# piezo-preamp-tickler_V2-RevD.net
KiCad netlist of a schematic drawn in EAGLE
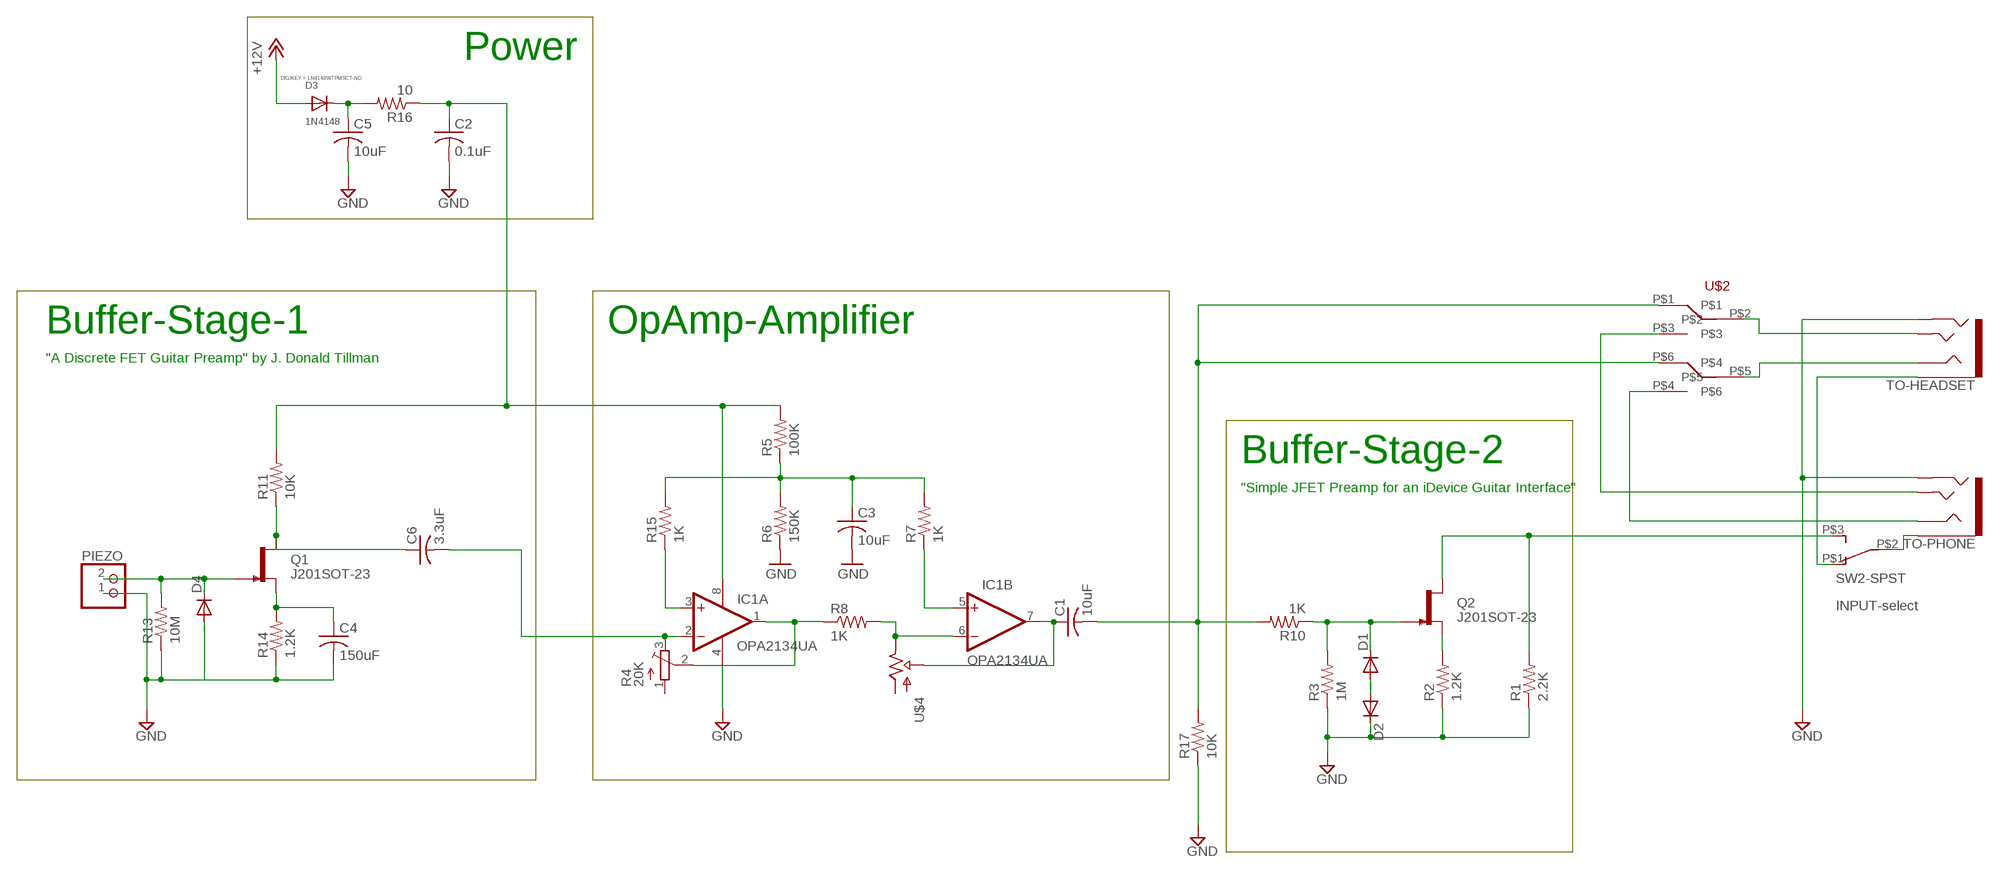
[diagram p0: schematic, sheet 1]
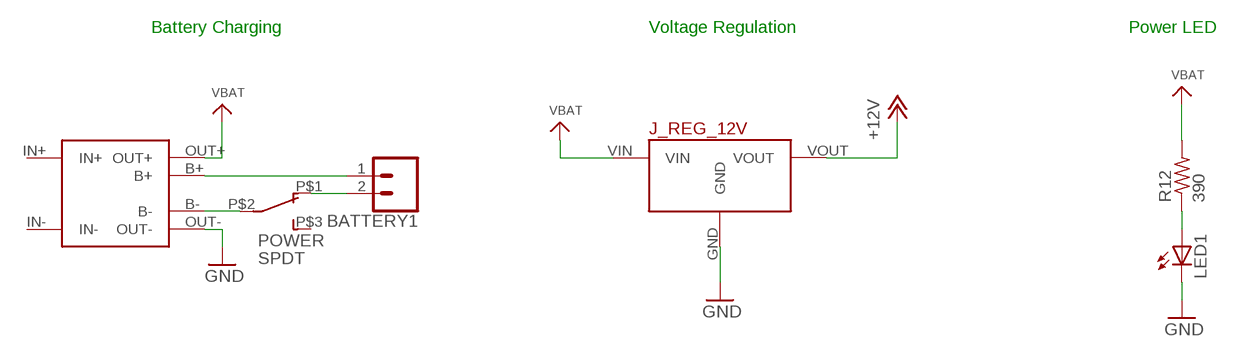
[diagram p1: schematic, sheet 2]

(export (version "E")
  (design (tool "Eeschema 10.0.6"))
  (components
    (comp (ref "BATTERY1")
      (value "CONN_02LOCK")
      (footprint "eagle-import:1X02_LOCK")
      (libsource (lib "eagle-import") (part "CONN_02LOCK"))
    )
    (comp (ref "J_REG_12V")
      (value "POLOLU_VOLTAGE_REGULATORS_3PIN")
      (footprint "eagle-import:POLOLU_5V-12V_STEPUP_U3V12F5-U3V12F12")
      (libsource (lib "eagle-import") (part "POLOLU_VOLTAGE_REGULATORS_3PIN"))
    )
    (comp (ref "LED1")
      (value "LED3MM")
      (footprint "eagle-import:LED3MM")
      (libsource (lib "eagle-import") (part "LED3MM"))
    )
    (comp (ref "POWER")
      (value "SPDT")
      (footprint "eagle-import:SWITCH_SPDT_CL-SB-12B")
      (libsource (lib "eagle-import") (part "SWITCH_SPDTCL-SB-12B"))
    )
    (comp (ref "R12")
      (value "390")
      (footprint "eagle-import:R0805")
      (libsource (lib "eagle-import") (part "R-US_R0805"))
    )
    (comp (ref "USB-LIPO-CHARGER")
      (value "TP4056-MODULE")
      (footprint "eagle-import:TP4056-LITHIUM-PROTECTED-MODULE")
      (libsource (lib "eagle-import") (part "TP4056-MODULE"))
    )
    (comp (ref "C1")
      (value "10uF")
      (footprint "eagle-import:C0805K")
      (libsource (lib "eagle-import") (part "C-USC0805K"))
    )
    (comp (ref "C2")
      (value "0.1uF")
      (footprint "eagle-import:C0805K")
      (libsource (lib "eagle-import") (part "C-USC0805K"))
    )
    (comp (ref "C3")
      (value "10uF")
      (footprint "eagle-import:C0805K")
      (libsource (lib "eagle-import") (part "C-USC0805K"))
    )
    (comp (ref "C4")
      (value "150uF")
      (footprint "eagle-import:C3216")
      (libsource (lib "eagle-import") (part "C-USC3216"))
    )
    (comp (ref "C5")
      (value "10uF")
      (footprint "eagle-import:C0805K")
      (libsource (lib "eagle-import") (part "C-USC0805K"))
    )
    (comp (ref "C6")
      (value "3.3uF")
      (footprint "eagle-import:C0805K")
      (libsource (lib "eagle-import") (part "C-USC0805K"))
    )
    (comp (ref "D1")
      (value "DIODE-SOD123")
      (footprint "eagle-import:SOD123")
      (libsource (lib "eagle-import") (part "DIODE-SOD123"))
    )
    (comp (ref "D2")
      (value "DIODE-SOD123")
      (footprint "eagle-import:SOD123")
      (libsource (lib "eagle-import") (part "DIODE-SOD123"))
    )
    (comp (ref "D3")
      (value "1N4148")
      (footprint "eagle-import:SOD-123")
      (fields (field (name "DIGIKEY") "1N4148WTPMSCT-ND"))
      (libsource (lib "eagle-import") (part "DIODESOD-123"))
    )
    (comp (ref "D4")
      (value "DIODE-SOD123")
      (footprint "eagle-import:SOD123")
      (libsource (lib "eagle-import") (part "DIODE-SOD123"))
    )
    (comp (ref "IC1")
      (value "OPA2134UA")
      (footprint "eagle-import:SO08")
      (libsource (lib "eagle-import") (part "OPA2UA134"))
    )
    (comp (ref "PIEZO")
      (value "JST_2PIN-THM")
      (footprint "eagle-import:JST-PH-2-THM")
      (libsource (lib "eagle-import") (part "JST_2PIN-THM"))
    )
    (comp (ref "Q1")
      (value "J201SOT-23")
      (footprint "eagle-import:SOT23-3")
      (libsource (lib "eagle-import") (part "J201SOT-23"))
    )
    (comp (ref "Q2")
      (value "J201SOT-23")
      (footprint "eagle-import:SOT23-3")
      (libsource (lib "eagle-import") (part "J201SOT-23"))
    )
    (comp (ref "R1")
      (value "2.2K")
      (footprint "eagle-import:R0603")
      (libsource (lib "eagle-import") (part "R-US_R0603"))
    )
    (comp (ref "R2")
      (value "1.2K")
      (footprint "eagle-import:R0603")
      (libsource (lib "eagle-import") (part "R-US_R0603"))
    )
    (comp (ref "R3")
      (value "1M")
      (footprint "eagle-import:R0603")
      (libsource (lib "eagle-import") (part "R-US_R0603"))
    )
    (comp (ref "R4")
      (value "20K")
      (footprint "eagle-import:TC33X")
      (libsource (lib "eagle-import") (part "TRIMPOTTC33X"))
    )
    (comp (ref "R5")
      (value "100K")
      (footprint "eagle-import:R0603")
      (libsource (lib "eagle-import") (part "R-US_R0603"))
    )
    (comp (ref "R6")
      (value "150K")
      (footprint "eagle-import:R0603")
      (libsource (lib "eagle-import") (part "R-US_R0603"))
    )
    (comp (ref "R7")
      (value "1K")
      (footprint "eagle-import:R0603")
      (libsource (lib "eagle-import") (part "R-US_R0603"))
    )
    (comp (ref "R8")
      (value "1K")
      (footprint "eagle-import:R0603")
      (libsource (lib "eagle-import") (part "R-US_R0603"))
    )
    (comp (ref "R10")
      (value "1K")
      (footprint "eagle-import:R0603")
      (libsource (lib "eagle-import") (part "R-US_R0603"))
    )
    (comp (ref "R11")
      (value "10K")
      (footprint "eagle-import:R0603")
      (libsource (lib "eagle-import") (part "R-US_R0603"))
    )
    (comp (ref "R13")
      (value "10M")
      (footprint "eagle-import:R0603")
      (libsource (lib "eagle-import") (part "R-US_R0603"))
    )
    (comp (ref "R14")
      (value "1.2K")
      (footprint "eagle-import:R0603")
      (libsource (lib "eagle-import") (part "R-US_R0603"))
    )
    (comp (ref "R15")
      (value "1K")
      (footprint "eagle-import:R0603")
      (libsource (lib "eagle-import") (part "R-US_R0603"))
    )
    (comp (ref "R16")
      (value "10")
      (footprint "eagle-import:R0603")
      (libsource (lib "eagle-import") (part "R-US_R0603"))
    )
    (comp (ref "R17")
      (value "10K")
      (footprint "eagle-import:R0603")
      (libsource (lib "eagle-import") (part "R-US_R0603"))
    )
    (comp (ref "SW2-SPST")
      (value "INPUT-select")
      (footprint "eagle-import:SWITCH_SPDT_CL-SB-12B")
      (libsource (lib "eagle-import") (part "SWITCH_SPDTCL-SB-12B"))
    )
    (comp (ref "TO-HEADSET")
      (value "AUDIO-JACK3LGPADS")
      (footprint "eagle-import:AUDIO-JACK-TRRS-SMD")
      (libsource (lib "eagle-import") (part "AUDIO-JACK3LGPADS"))
    )
    (comp (ref "TO-PHONE")
      (value "AUDIO-JACK3LGPADS")
      (footprint "eagle-import:AUDIO-JACK-TRRS-SMD")
      (libsource (lib "eagle-import") (part "AUDIO-JACK3LGPADS"))
    )
    (comp (ref "U$2")
      (value "SWITCH_DPDT")
      (footprint "eagle-import:SWITCH_DPDT_CL-SB-12B")
      (libsource (lib "eagle-import") (part "SWITCH_DPDT"))
    )
    (comp (ref "U$4")
      (value "POT")
      (footprint "eagle-import:ALPS_POT")
      (libsource (lib "eagle-import") (part "POT"))
    )
  )
  (nets
    (net (code "1") (name "+12V") (class "Default")
      (node (ref "D3") (pin "A") (pinfunction "A_A") (pintype "passive"))
      (node (ref "J_REG_12V") (pin "VOUT") (pinfunction "VOUT_VOUT") (pintype "bidirectional"))
    )
    (net (code "2") (name "GND") (class "Default")
      (node (ref "C2") (pin "2") (pinfunction "2_2") (pintype "passive"))
      (node (ref "C3") (pin "2") (pinfunction "2_2") (pintype "passive"))
      (node (ref "C4") (pin "2") (pinfunction "2_2") (pintype "passive"))
      (node (ref "C5") (pin "2") (pinfunction "2_2") (pintype "passive"))
      (node (ref "D2") (pin "C") (pinfunction "C_C") (pintype "passive"))
      (node (ref "D4") (pin "A") (pinfunction "A_A") (pintype "passive"))
      (node (ref "IC1") (pin "4") (pinfunction "V-_4") (pintype "power_in"))
      (node (ref "J_REG_12V") (pin "GND") (pinfunction "GND_GND") (pintype "bidirectional"))
      (node (ref "LED1") (pin "K") (pinfunction "C_K") (pintype "passive"))
      (node (ref "PIEZO") (pin "1") (pinfunction "2_1") (pintype "passive"))
      (node (ref "R1") (pin "1") (pinfunction "1_1") (pintype "passive"))
      (node (ref "R13") (pin "1") (pinfunction "1_1") (pintype "passive"))
      (node (ref "R14") (pin "1") (pinfunction "1_1") (pintype "passive"))
      (node (ref "R17") (pin "1") (pinfunction "1_1") (pintype "passive"))
      (node (ref "R2") (pin "1") (pinfunction "1_1") (pintype "passive"))
      (node (ref "R3") (pin "1") (pinfunction "1_1") (pintype "passive"))
      (node (ref "R6") (pin "1") (pinfunction "1_1") (pintype "passive"))
      (node (ref "TO-HEADSET") (pin "RING2") (pinfunction "RING2_RING2") (pintype "bidirectional"))
      (node (ref "TO-PHONE") (pin "RING2") (pinfunction "RING2_RING2") (pintype "bidirectional"))
      (node (ref "USB-LIPO-CHARGER") (pin "OUT-") (pinfunction "OUT-_OUT-") (pintype "power_in"))
    )
    (net (code "3") (name "IN+") (class "Default")
      (node (ref "USB-LIPO-CHARGER") (pin "IN+") (pinfunction "IN+_IN+") (pintype "power_in"))
    )
    (net (code "4") (name "IN-") (class "Default")
      (node (ref "USB-LIPO-CHARGER") (pin "IN-") (pinfunction "IN-_IN-") (pintype "power_in"))
    )
    (net (code "5") (name "Net-(BATTERY1-Pad1)") (class "Default")
      (node (ref "BATTERY1") (pin "1") (pinfunction "1_1") (pintype "passive"))
      (node (ref "USB-LIPO-CHARGER") (pin "B+") (pinfunction "B+_B+") (pintype "power_in"))
    )
    (net (code "6") (name "Net-(C3-Pad1)") (class "Default")
      (node (ref "C3") (pin "1") (pinfunction "1_1") (pintype "passive"))
      (node (ref "R15") (pin "2") (pinfunction "2_2") (pintype "passive"))
      (node (ref "R5") (pin "1") (pinfunction "1_1") (pintype "passive"))
      (node (ref "R6") (pin "2") (pinfunction "2_2") (pintype "passive"))
      (node (ref "R7") (pin "2") (pinfunction "2_2") (pintype "passive"))
    )
    (net (code "7") (name "Net-(C5-Pad1)") (class "Default")
      (node (ref "C5") (pin "1") (pinfunction "1_1") (pintype "passive"))
      (node (ref "D3") (pin "C") (pinfunction "C_C") (pintype "passive"))
      (node (ref "R16") (pin "2") (pinfunction "2_2") (pintype "passive"))
    )
    (net (code "8") (name "Net-(D1-PadA)") (class "Default")
      (node (ref "D1") (pin "A") (pinfunction "A_A") (pintype "passive"))
      (node (ref "D2") (pin "A") (pinfunction "A_A") (pintype "passive"))
    )
    (net (code "9") (name "Net-(IC1A-+IN)") (class "Default")
      (node (ref "IC1") (pin "3") (pinfunction "+IN_3") (pintype "input"))
      (node (ref "R15") (pin "1") (pinfunction "1_1") (pintype "passive"))
    )
    (net (code "10") (name "Net-(IC1A--IN)") (class "Default")
      (node (ref "C6") (pin "2") (pinfunction "2_2") (pintype "passive"))
      (node (ref "IC1") (pin "2") (pinfunction "-IN_2") (pintype "input"))
      (node (ref "R4") (pin "3") (pinfunction "E_3") (pintype "passive"))
    )
    (net (code "11") (name "Net-(IC1A-OUT)") (class "Default")
      (node (ref "IC1") (pin "1") (pinfunction "OUT_1") (pintype "output"))
      (node (ref "R4") (pin "2") (pinfunction "S_2") (pintype "passive"))
      (node (ref "R8") (pin "1") (pinfunction "1_1") (pintype "passive"))
    )
    (net (code "12") (name "Net-(IC1A-V+)") (class "Default")
      (node (ref "C2") (pin "1") (pinfunction "1_1") (pintype "passive"))
      (node (ref "IC1") (pin "8") (pinfunction "V+_8") (pintype "power_in"))
      (node (ref "R11") (pin "2") (pinfunction "2_2") (pintype "passive"))
      (node (ref "R16") (pin "1") (pinfunction "1_1") (pintype "passive"))
      (node (ref "R5") (pin "2") (pinfunction "2_2") (pintype "passive"))
    )
    (net (code "13") (name "Net-(IC1B-+IN)") (class "Default")
      (node (ref "IC1") (pin "5") (pinfunction "+IN_5") (pintype "input"))
      (node (ref "R7") (pin "1") (pinfunction "1_1") (pintype "passive"))
    )
    (net (code "14") (name "Net-(IC1B--IN)") (class "Default")
      (node (ref "IC1") (pin "6") (pinfunction "-IN_6") (pintype "input"))
      (node (ref "R8") (pin "2") (pinfunction "2_2") (pintype "passive"))
      (node (ref "U$4") (pin "P$1") (pinfunction "OUT_P$1") (pintype "passive"))
    )
    (net (code "15") (name "Net-(IC1B-OUT)") (class "Default")
      (node (ref "C1") (pin "1") (pinfunction "1_1") (pintype "passive"))
      (node (ref "IC1") (pin "7") (pinfunction "OUT_7") (pintype "output"))
      (node (ref "U$4") (pin "P$2") (pinfunction "WIPER_P$2") (pintype "passive"))
    )
    (net (code "16") (name "Net-(LED1-PadA)") (class "Default")
      (node (ref "LED1") (pin "A") (pinfunction "A_A") (pintype "passive"))
      (node (ref "R12") (pin "1") (pinfunction "1_1") (pintype "passive"))
    )
    (net (code "17") (name "Net-(PIEZO-1)") (class "Default")
      (node (ref "D4") (pin "C") (pinfunction "C_C") (pintype "passive"))
      (node (ref "PIEZO") (pin "2") (pinfunction "1_2") (pintype "passive"))
      (node (ref "Q1") (pin "3") (pinfunction "G_3") (pintype "passive"))
      (node (ref "R13") (pin "2") (pinfunction "2_2") (pintype "passive"))
    )
    (net (code "18") (name "Net-(POWER-1)") (class "Default")
      (node (ref "BATTERY1") (pin "2") (pinfunction "2_2") (pintype "passive"))
      (node (ref "POWER") (pin "P$1") (pinfunction "1_P$1") (pintype "passive"))
    )
    (net (code "19") (name "Net-(POWER-2)") (class "Default")
      (node (ref "POWER") (pin "P$2") (pinfunction "2_P$2") (pintype "passive"))
      (node (ref "USB-LIPO-CHARGER") (pin "B-") (pinfunction "B-_B-") (pintype "power_in"))
    )
    (net (code "20") (name "Net-(Q1-D)") (class "Default")
      (node (ref "C6") (pin "1") (pinfunction "1_1") (pintype "passive"))
      (node (ref "Q1") (pin "1") (pinfunction "D_1") (pintype "passive"))
      (node (ref "R11") (pin "1") (pinfunction "1_1") (pintype "passive"))
    )
    (net (code "21") (name "Net-(Q1-S)") (class "Default")
      (node (ref "C4") (pin "1") (pinfunction "1_1") (pintype "passive"))
      (node (ref "Q1") (pin "2") (pinfunction "S_2") (pintype "passive"))
      (node (ref "R14") (pin "2") (pinfunction "2_2") (pintype "passive"))
    )
    (net (code "22") (name "Net-(Q2-D)") (class "Default")
      (node (ref "Q2") (pin "1") (pinfunction "D_1") (pintype "passive"))
      (node (ref "R1") (pin "2") (pinfunction "2_2") (pintype "passive"))
      (node (ref "SW2-SPST") (pin "P$3") (pinfunction "3_P$3") (pintype "passive"))
    )
    (net (code "23") (name "Net-(Q2-G)") (class "Default")
      (node (ref "D1") (pin "C") (pinfunction "C_C") (pintype "passive"))
      (node (ref "Q2") (pin "3") (pinfunction "G_3") (pintype "passive"))
      (node (ref "R10") (pin "1") (pinfunction "1_1") (pintype "passive"))
      (node (ref "R3") (pin "2") (pinfunction "2_2") (pintype "passive"))
    )
    (net (code "24") (name "Net-(Q2-S)") (class "Default")
      (node (ref "Q2") (pin "2") (pinfunction "S_2") (pintype "passive"))
      (node (ref "R2") (pin "2") (pinfunction "2_2") (pintype "passive"))
    )
    (net (code "25") (name "Net-(SW2-SPST-1)") (class "Default")
      (node (ref "SW2-SPST") (pin "P$1") (pinfunction "1_P$1") (pintype "passive"))
      (node (ref "TO-HEADSET") (pin "EARTH") (pinfunction "EARTH_EARTH") (pintype "bidirectional"))
    )
    (net (code "26") (name "Net-(SW2-SPST-2)") (class "Default")
      (node (ref "SW2-SPST") (pin "P$2") (pinfunction "2_P$2") (pintype "passive"))
      (node (ref "TO-PHONE") (pin "EARTH") (pinfunction "EARTH_EARTH") (pintype "bidirectional"))
    )
    (net (code "27") (name "Net-(TO-HEADSET-PadRING1)") (class "Default")
      (node (ref "TO-HEADSET") (pin "RING1") (pinfunction "RING1_RING1") (pintype "bidirectional"))
      (node (ref "U$2") (pin "P$5") (pinfunction "P$5_P$5") (pintype "bidirectional"))
    )
    (net (code "28") (name "Net-(TO-HEADSET-PadTIP)") (class "Default")
      (node (ref "TO-HEADSET") (pin "TIP") (pinfunction "TIP_TIP") (pintype "bidirectional"))
      (node (ref "U$2") (pin "P$2") (pinfunction "P$2_P$2") (pintype "bidirectional"))
    )
    (net (code "29") (name "Net-(TO-PHONE-PadTIP)") (class "Default")
      (node (ref "TO-PHONE") (pin "TIP") (pinfunction "TIP_TIP") (pintype "bidirectional"))
      (node (ref "U$2") (pin "P$3") (pinfunction "P$3_P$3") (pintype "bidirectional"))
    )
    (net (code "30") (name "Net-(U$2-P$4)") (class "Default")
      (node (ref "C1") (pin "2") (pinfunction "2_2") (pintype "passive"))
      (node (ref "R10") (pin "2") (pinfunction "2_2") (pintype "passive"))
      (node (ref "R17") (pin "2") (pinfunction "2_2") (pintype "passive"))
      (node (ref "U$2") (pin "P$1") (pinfunction "P$1_P$1") (pintype "bidirectional"))
      (node (ref "U$2") (pin "P$6") (pinfunction "P$4_P$6") (pintype "bidirectional"))
    )
    (net (code "31") (name "Net-(U$2-P$6)") (class "Default")
      (node (ref "TO-PHONE") (pin "RING1") (pinfunction "RING1_RING1") (pintype "bidirectional"))
      (node (ref "U$2") (pin "P$4") (pinfunction "P$6_P$4") (pintype "bidirectional"))
    )
    (net (code "32") (name "VBAT") (class "Default")
      (node (ref "J_REG_12V") (pin "VIN") (pinfunction "VIN_VIN") (pintype "bidirectional"))
      (node (ref "R12") (pin "2") (pinfunction "2_2") (pintype "passive"))
      (node (ref "USB-LIPO-CHARGER") (pin "OUT+") (pinfunction "OUT+_OUT+") (pintype "power_in"))
    )
    (net (code "33") (name "unconnected-(POWER-3-PadP$3)") (class "Default")
      (node (ref "POWER") (pin "P$3") (pinfunction "3_P$3") (pintype "passive"))
    )
    (net (code "34") (name "unconnected-(R4-A-Pad1)") (class "Default")
      (node (ref "R4") (pin "1") (pinfunction "A_1") (pintype "passive"))
    )
    (net (code "35") (name "unconnected-(U$4-IN-PadP$3)") (class "Default")
      (node (ref "U$4") (pin "P$3") (pinfunction "IN_P$3") (pintype "passive"))
    )
  )
)
